# cpu.net
KiCad netlist of a schematic drawn in EAGLE
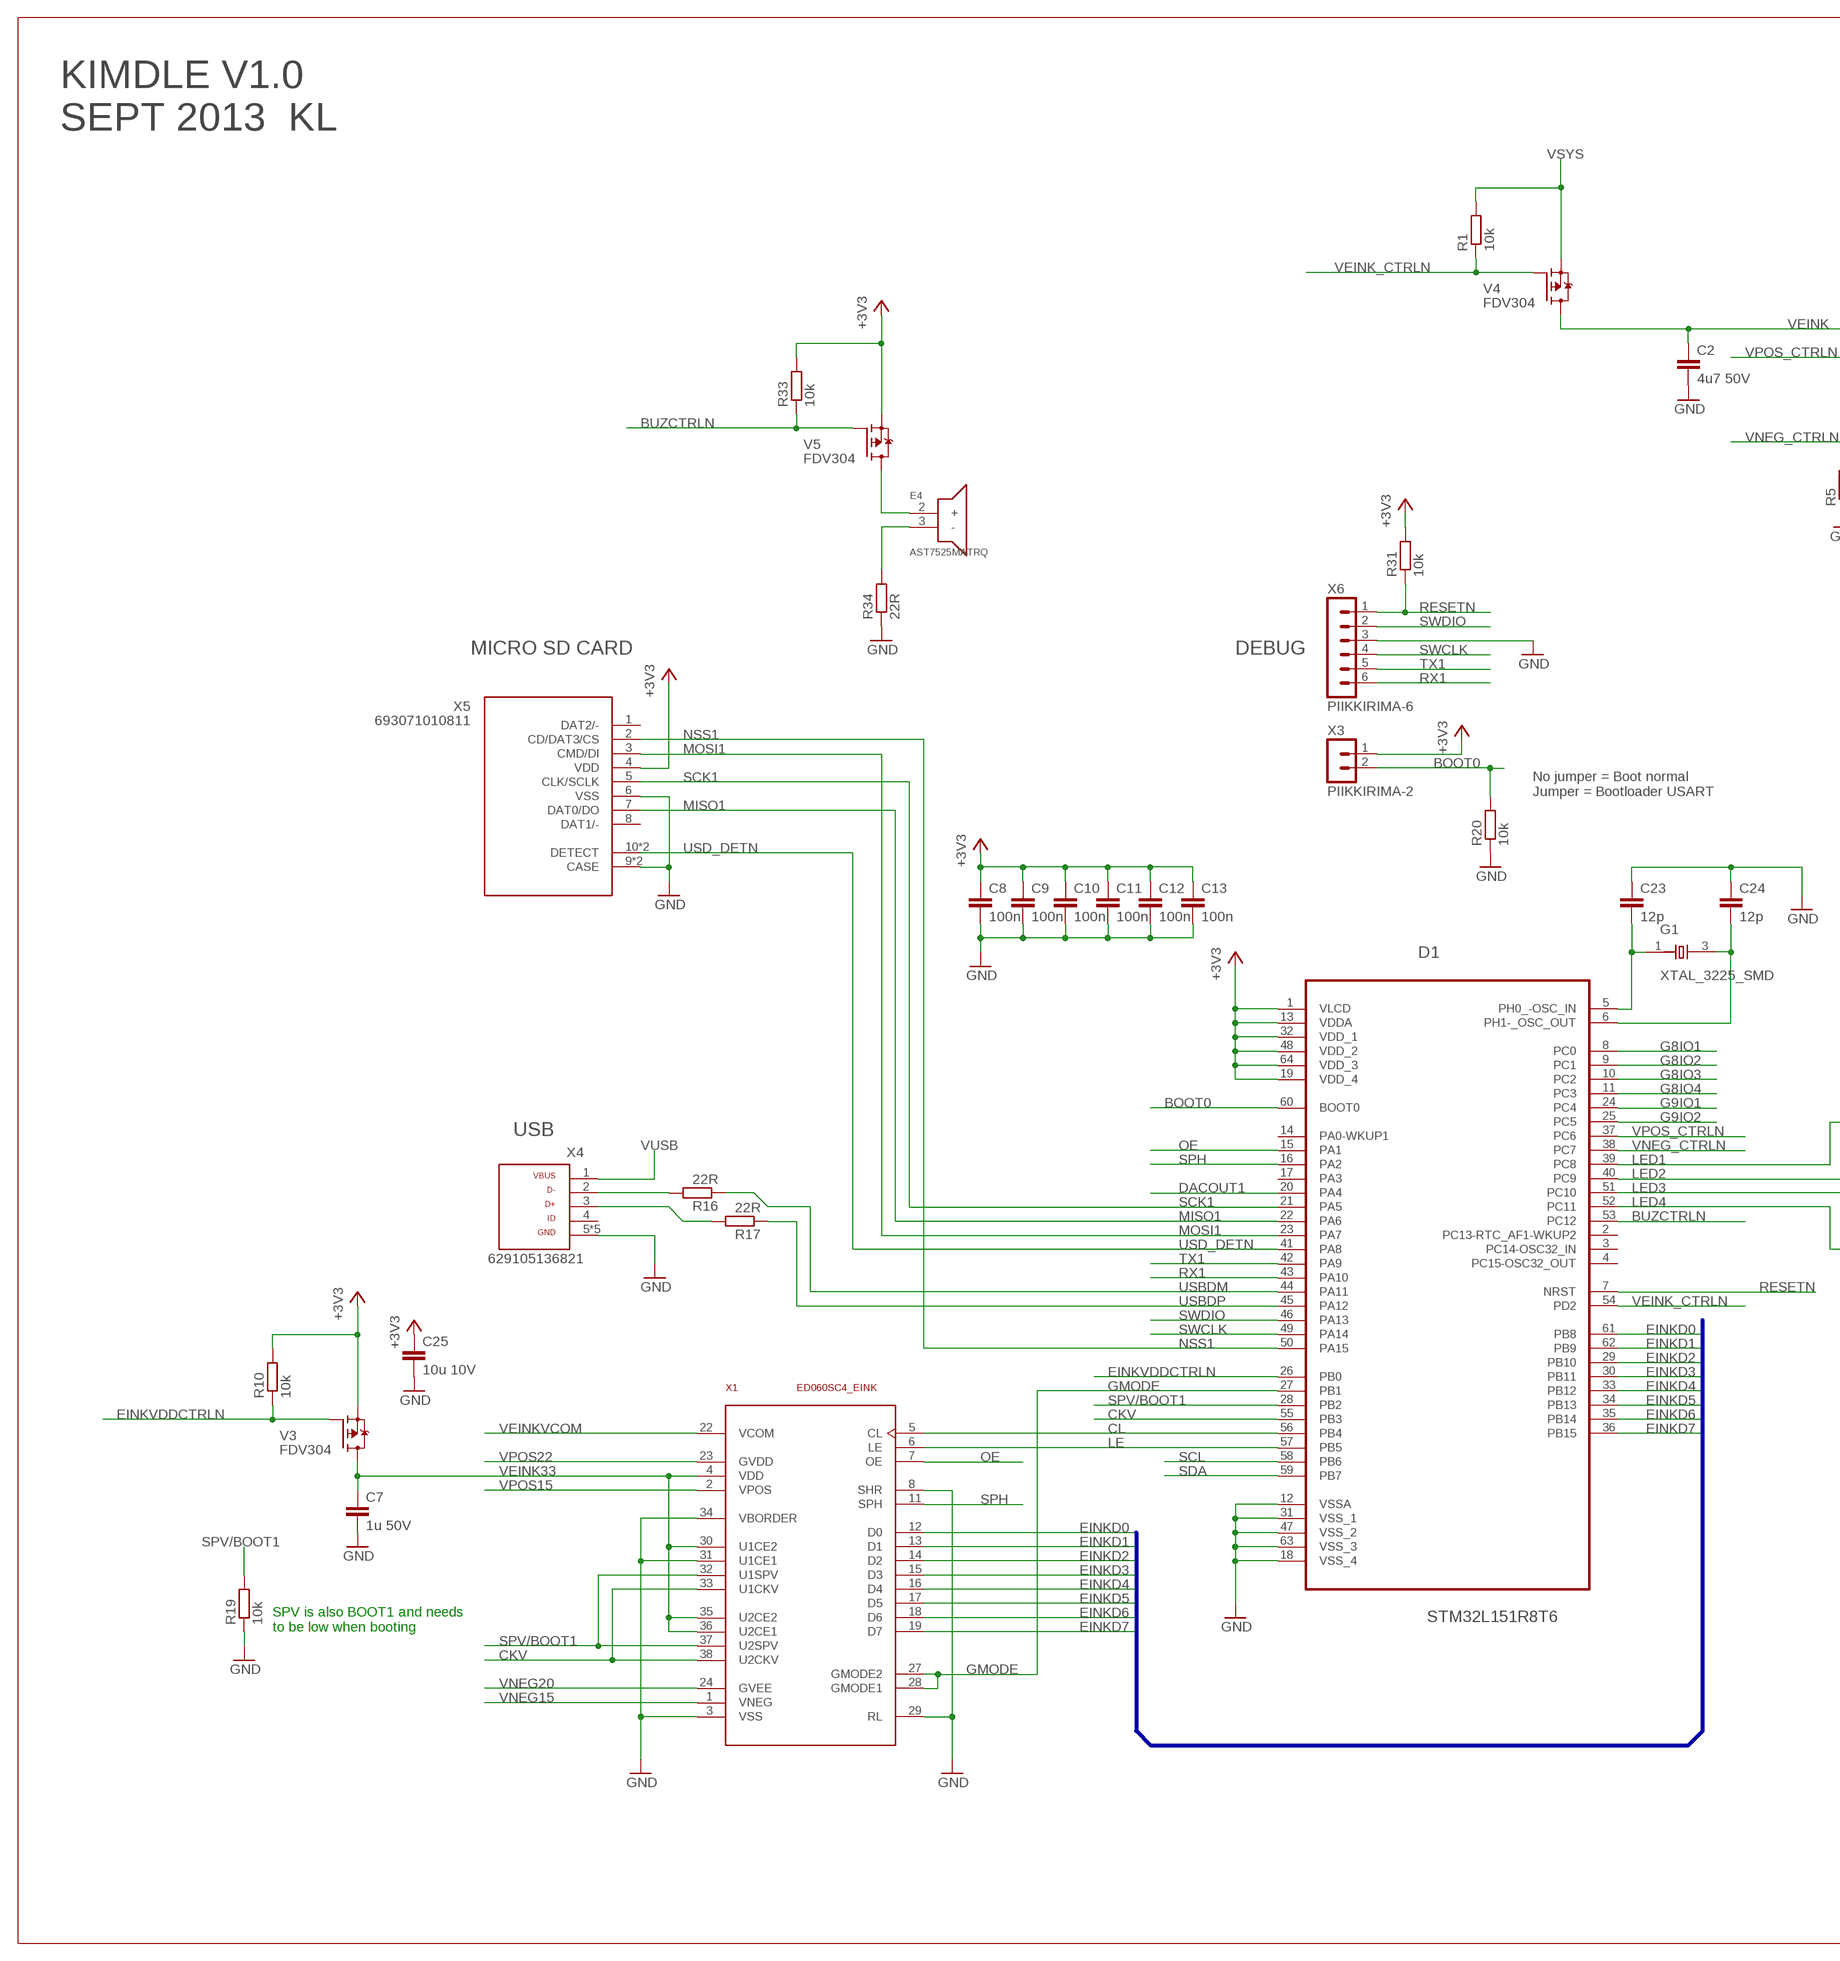
[diagram p0: schematic, sheet 1, part 1 of 2]
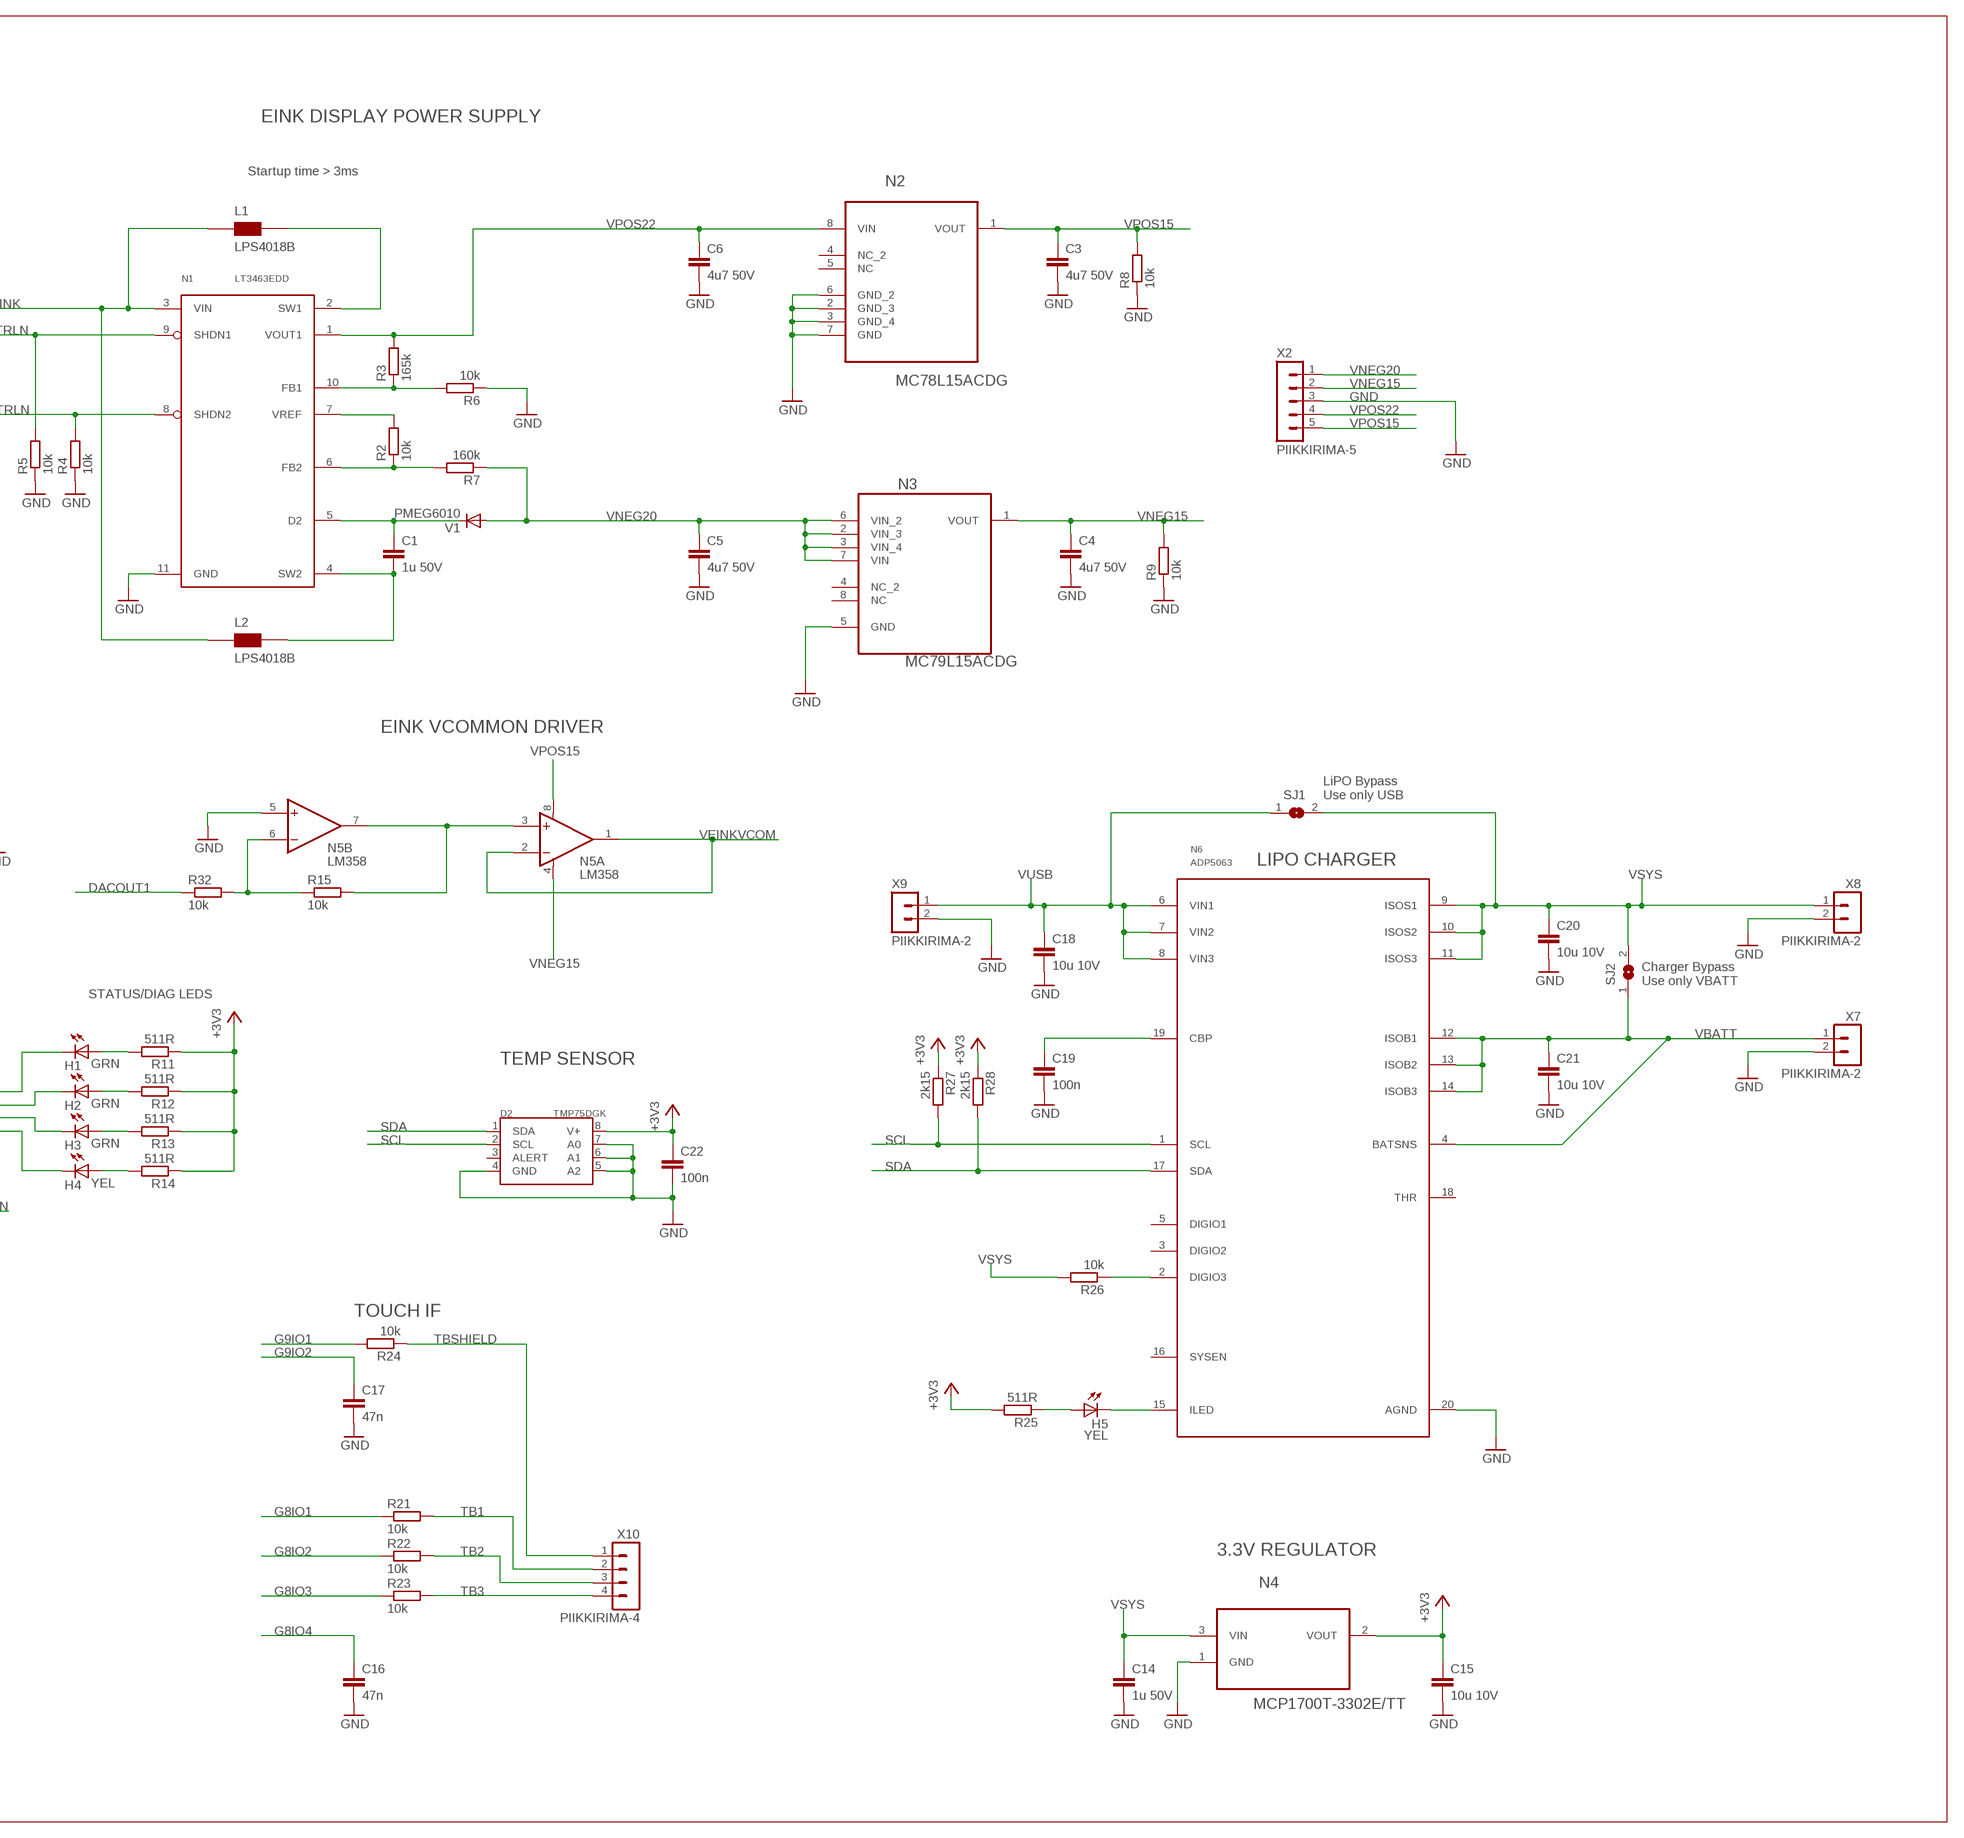
[diagram p1: schematic, sheet 1, part 2 of 2]

(export (version "E")
  (design (tool "Eeschema 10.0.6"))
  (components
    (comp (ref "C1")
      (value "1u 50V")
      (footprint "eagle-import:C0805")
      (libsource (lib "eagle-import") (part "C-EUC0805"))
    )
    (comp (ref "C2")
      (value "4u7 50V")
      (footprint "eagle-import:C0805")
      (libsource (lib "eagle-import") (part "C-EUC0805"))
    )
    (comp (ref "C3")
      (value "4u7 50V")
      (footprint "eagle-import:C0805")
      (libsource (lib "eagle-import") (part "C-EUC0805"))
    )
    (comp (ref "C4")
      (value "4u7 50V")
      (footprint "eagle-import:C0805")
      (libsource (lib "eagle-import") (part "C-EUC0805"))
    )
    (comp (ref "C5")
      (value "4u7 50V")
      (footprint "eagle-import:C0805")
      (libsource (lib "eagle-import") (part "C-EUC0805"))
    )
    (comp (ref "C6")
      (value "4u7 50V")
      (footprint "eagle-import:C0805")
      (libsource (lib "eagle-import") (part "C-EUC0805"))
    )
    (comp (ref "C7")
      (value "1u 50V")
      (footprint "eagle-import:C0805")
      (libsource (lib "eagle-import") (part "C-EUC0805"))
    )
    (comp (ref "C8")
      (value "100n")
      (footprint "eagle-import:C0603")
      (libsource (lib "eagle-import") (part "C-EUC0603"))
    )
    (comp (ref "C9")
      (value "100n")
      (footprint "eagle-import:C0603")
      (libsource (lib "eagle-import") (part "C-EUC0603"))
    )
    (comp (ref "C10")
      (value "100n")
      (footprint "eagle-import:C0603")
      (libsource (lib "eagle-import") (part "C-EUC0603"))
    )
    (comp (ref "C11")
      (value "100n")
      (footprint "eagle-import:C0603")
      (libsource (lib "eagle-import") (part "C-EUC0603"))
    )
    (comp (ref "C12")
      (value "100n")
      (footprint "eagle-import:C0603")
      (libsource (lib "eagle-import") (part "C-EUC0603"))
    )
    (comp (ref "C13")
      (value "100n")
      (footprint "eagle-import:C0603")
      (libsource (lib "eagle-import") (part "C-EUC0603"))
    )
    (comp (ref "C14")
      (value "1u 50V")
      (footprint "eagle-import:C0805")
      (libsource (lib "eagle-import") (part "C-EUC0805"))
    )
    (comp (ref "C15")
      (value "10u 10V")
      (footprint "eagle-import:C0805")
      (libsource (lib "eagle-import") (part "C-EUC0805"))
    )
    (comp (ref "C16")
      (value "47n")
      (footprint "eagle-import:C0805")
      (libsource (lib "eagle-import") (part "C-EUC0805"))
    )
    (comp (ref "C17")
      (value "47n")
      (footprint "eagle-import:C0805")
      (libsource (lib "eagle-import") (part "C-EUC0805"))
    )
    (comp (ref "C18")
      (value "10u 10V")
      (footprint "eagle-import:C0805")
      (libsource (lib "eagle-import") (part "C-EUC0805"))
    )
    (comp (ref "C19")
      (value "100n")
      (footprint "eagle-import:C0603")
      (libsource (lib "eagle-import") (part "C-EUC0603"))
    )
    (comp (ref "C20")
      (value "10u 10V")
      (footprint "eagle-import:C0805")
      (libsource (lib "eagle-import") (part "C-EUC0805"))
    )
    (comp (ref "C21")
      (value "10u 10V")
      (footprint "eagle-import:C0805")
      (libsource (lib "eagle-import") (part "C-EUC0805"))
    )
    (comp (ref "C22")
      (value "100n")
      (footprint "eagle-import:C0603")
      (libsource (lib "eagle-import") (part "C-EUC0603"))
    )
    (comp (ref "C23")
      (value "12p")
      (footprint "eagle-import:C0603")
      (libsource (lib "eagle-import") (part "C-EUC0603"))
    )
    (comp (ref "C24")
      (value "12p")
      (footprint "eagle-import:C0603")
      (libsource (lib "eagle-import") (part "C-EUC0603"))
    )
    (comp (ref "C25")
      (value "10u 10V")
      (footprint "eagle-import:C0805")
      (libsource (lib "eagle-import") (part "C-EUC0805"))
    )
    (comp (ref "D1")
      (value "STM32L151R8T6")
      (footprint "eagle-import:QFP50P1200X1200X160-64N")
      (libsource (lib "eagle-import") (part "STM32L151R8T6"))
    )
    (comp (ref "D2")
      (value "TMP75DGK")
      (footprint "eagle-import:MSOP8")
      (libsource (lib "eagle-import") (part "TMP75DGK"))
    )
    (comp (ref "E4")
      (value "AST7525MATRQ")
      (footprint "eagle-import:AST7525MATRQ")
      (libsource (lib "eagle-import") (part "AST7525MATRQ"))
    )
    (comp (ref "G1")
      (value "XTAL_3225_SMD")
      (footprint "eagle-import:X_3225")
      (libsource (lib "eagle-import") (part "XTAL_3225_SMD"))
    )
    (comp (ref "H1")
      (value "GRN")
      (footprint "eagle-import:CHIP-LED0603")
      (libsource (lib "eagle-import") (part "LEDCHIP-LED0603"))
    )
    (comp (ref "H2")
      (value "GRN")
      (footprint "eagle-import:CHIP-LED0603")
      (libsource (lib "eagle-import") (part "LEDCHIP-LED0603"))
    )
    (comp (ref "H3")
      (value "GRN")
      (footprint "eagle-import:CHIP-LED0603")
      (libsource (lib "eagle-import") (part "LEDCHIP-LED0603"))
    )
    (comp (ref "H4")
      (value "YEL")
      (footprint "eagle-import:CHIP-LED0603")
      (libsource (lib "eagle-import") (part "LEDCHIP-LED0603"))
    )
    (comp (ref "H5")
      (value "YEL")
      (footprint "eagle-import:CHIP-LED0603")
      (libsource (lib "eagle-import") (part "LEDCHIP-LED0603"))
    )
    (comp (ref "L1")
      (value "LPS4018B")
      (footprint "eagle-import:LPS4018_V2")
      (libsource (lib "eagle-import") (part "LPS4018B"))
    )
    (comp (ref "L2")
      (value "LPS4018B")
      (footprint "eagle-import:LPS4018_V2")
      (libsource (lib "eagle-import") (part "LPS4018B"))
    )
    (comp (ref "N1")
      (value "LT3463EDD")
      (footprint "eagle-import:DFN300X300X80-11N")
      (libsource (lib "eagle-import") (part "LT3463EDD"))
    )
    (comp (ref "N2")
      (value "MC78L15ACDG")
      (footprint "eagle-import:SOIC127P600X175-8N")
      (libsource (lib "eagle-import") (part "MC78L15ACDG"))
    )
    (comp (ref "N3")
      (value "MC79L15ACDG")
      (footprint "eagle-import:SOIC127P600X175-8N")
      (libsource (lib "eagle-import") (part "MC79L15ACDG"))
    )
    (comp (ref "N4")
      (value "MCP1700T-3302E/TT")
      (footprint "eagle-import:SOT95P237X112-3N")
      (libsource (lib "eagle-import") (part "MCP1700T-3302E/TT"))
    )
    (comp (ref "N5")
      (value "LM358")
      (footprint "eagle-import:SOP65P490X110-8N")
      (libsource (lib "eagle-import") (part "MAX412CPAMSOP"))
    )
    (comp (ref "N6")
      (value "ADP5063")
      (footprint "eagle-import:QFN50P400X400X80-21N")
      (libsource (lib "eagle-import") (part "ADP5063"))
    )
    (comp (ref "R1")
      (value "10k")
      (footprint "eagle-import:R0603")
      (libsource (lib "eagle-import") (part "R-EU_R0603"))
    )
    (comp (ref "R2")
      (value "10k")
      (footprint "eagle-import:R0603")
      (libsource (lib "eagle-import") (part "R-EU_R0603"))
    )
    (comp (ref "R3")
      (value "165k")
      (footprint "eagle-import:R0603")
      (libsource (lib "eagle-import") (part "R-EU_R0603"))
    )
    (comp (ref "R4")
      (value "10k")
      (footprint "eagle-import:R0603")
      (libsource (lib "eagle-import") (part "R-EU_R0603"))
    )
    (comp (ref "R5")
      (value "10k")
      (footprint "eagle-import:R0603")
      (libsource (lib "eagle-import") (part "R-EU_R0603"))
    )
    (comp (ref "R6")
      (value "10k")
      (footprint "eagle-import:R0603")
      (libsource (lib "eagle-import") (part "R-EU_R0603"))
    )
    (comp (ref "R7")
      (value "160k")
      (footprint "eagle-import:R0603")
      (libsource (lib "eagle-import") (part "R-EU_R0603"))
    )
    (comp (ref "R8")
      (value "10k")
      (footprint "eagle-import:R0603")
      (libsource (lib "eagle-import") (part "R-EU_R0603"))
    )
    (comp (ref "R9")
      (value "10k")
      (footprint "eagle-import:R0603")
      (libsource (lib "eagle-import") (part "R-EU_R0603"))
    )
    (comp (ref "R10")
      (value "10k")
      (footprint "eagle-import:R0603")
      (libsource (lib "eagle-import") (part "R-EU_R0603"))
    )
    (comp (ref "R11")
      (value "511R")
      (footprint "eagle-import:R0603")
      (libsource (lib "eagle-import") (part "R-EU_R0603"))
    )
    (comp (ref "R12")
      (value "511R")
      (footprint "eagle-import:R0603")
      (libsource (lib "eagle-import") (part "R-EU_R0603"))
    )
    (comp (ref "R13")
      (value "511R")
      (footprint "eagle-import:R0603")
      (libsource (lib "eagle-import") (part "R-EU_R0603"))
    )
    (comp (ref "R14")
      (value "511R")
      (footprint "eagle-import:R0603")
      (libsource (lib "eagle-import") (part "R-EU_R0603"))
    )
    (comp (ref "R15")
      (value "10k")
      (footprint "eagle-import:R0603")
      (libsource (lib "eagle-import") (part "R-EU_R0603"))
    )
    (comp (ref "R16")
      (value "22R")
      (footprint "eagle-import:R0603")
      (libsource (lib "eagle-import") (part "R-EU_R0603"))
    )
    (comp (ref "R17")
      (value "22R")
      (footprint "eagle-import:R0603")
      (libsource (lib "eagle-import") (part "R-EU_R0603"))
    )
    (comp (ref "R19")
      (value "10k")
      (footprint "eagle-import:R0603")
      (libsource (lib "eagle-import") (part "R-EU_R0603"))
    )
    (comp (ref "R20")
      (value "10k")
      (footprint "eagle-import:R0603")
      (libsource (lib "eagle-import") (part "R-EU_R0603"))
    )
    (comp (ref "R21")
      (value "10k")
      (footprint "eagle-import:R0603")
      (libsource (lib "eagle-import") (part "R-EU_R0603"))
    )
    (comp (ref "R22")
      (value "10k")
      (footprint "eagle-import:R0603")
      (libsource (lib "eagle-import") (part "R-EU_R0603"))
    )
    (comp (ref "R23")
      (value "10k")
      (footprint "eagle-import:R0603")
      (libsource (lib "eagle-import") (part "R-EU_R0603"))
    )
    (comp (ref "R24")
      (value "10k")
      (footprint "eagle-import:R0603")
      (libsource (lib "eagle-import") (part "R-EU_R0603"))
    )
    (comp (ref "R25")
      (value "511R")
      (footprint "eagle-import:R0603")
      (libsource (lib "eagle-import") (part "R-EU_R0603"))
    )
    (comp (ref "R26")
      (value "10k")
      (footprint "eagle-import:R0603")
      (libsource (lib "eagle-import") (part "R-EU_R0603"))
    )
    (comp (ref "R27")
      (value "2k15")
      (footprint "eagle-import:R0603")
      (libsource (lib "eagle-import") (part "R-EU_R0603"))
    )
    (comp (ref "R28")
      (value "2k15")
      (footprint "eagle-import:R0603")
      (libsource (lib "eagle-import") (part "R-EU_R0603"))
    )
    (comp (ref "R31")
      (value "10k")
      (footprint "eagle-import:R0603")
      (libsource (lib "eagle-import") (part "R-EU_R0603"))
    )
    (comp (ref "R32")
      (value "10k")
      (footprint "eagle-import:R0603")
      (libsource (lib "eagle-import") (part "R-EU_R0603"))
    )
    (comp (ref "R33")
      (value "10k")
      (footprint "eagle-import:R0603")
      (libsource (lib "eagle-import") (part "R-EU_R0603"))
    )
    (comp (ref "R34")
      (value "22R")
      (footprint "eagle-import:R0603")
      (libsource (lib "eagle-import") (part "R-EU_R0603"))
    )
    (comp (ref "SJ1")
      (value "SJ")
      (footprint "eagle-import:SJ-SMALL")
      (libsource (lib "eagle-import") (part "SJ"))
    )
    (comp (ref "SJ2")
      (value "SJ")
      (footprint "eagle-import:SJ-SMALL")
      (libsource (lib "eagle-import") (part "SJ"))
    )
    (comp (ref "V1")
      (value "PMEG6010")
      (footprint "eagle-import:SOD323-R")
      (libsource (lib "eagle-import") (part "DIODE-SOD323-R"))
    )
    (comp (ref "V3")
      (value "FDV304")
      (footprint "eagle-import:SOT23")
      (libsource (lib "eagle-import") (part "DMG2307LSOT23"))
    )
    (comp (ref "V4")
      (value "FDV304")
      (footprint "eagle-import:SOT23")
      (libsource (lib "eagle-import") (part "DMG2307LSOT23"))
    )
    (comp (ref "V5")
      (value "FDV304")
      (footprint "eagle-import:SOT23")
      (libsource (lib "eagle-import") (part "DMG2307LSOT23"))
    )
    (comp (ref "X1")
      (value "ED060SC4_EINK")
      (footprint "eagle-import:FH26-39S-0.3SHW")
      (libsource (lib "eagle-import") (part "ED060SC4_EINK"))
    )
    (comp (ref "X2")
      (value "PIIKKIRIMA-5")
      (footprint "eagle-import:PIIKKIRIMA-5")
      (libsource (lib "eagle-import") (part "PIIKKIRIMA-5"))
    )
    (comp (ref "X3")
      (value "PIIKKIRIMA-2")
      (footprint "eagle-import:PIIKKIRIMA-2")
      (libsource (lib "eagle-import") (part "PIIKKIRIMA-2"))
    )
    (comp (ref "X4")
      (value "629105136821")
      (footprint "eagle-import:629105136821")
      (libsource (lib "eagle-import") (part "629105136821"))
    )
    (comp (ref "X5")
      (value "693071010811")
      (footprint "eagle-import:693071010811")
      (libsource (lib "eagle-import") (part "693071010811"))
    )
    (comp (ref "X6")
      (value "PIIKKIRIMA-6")
      (footprint "eagle-import:PIIKKIRIMA-6")
      (libsource (lib "eagle-import") (part "PIIKKIRIMA-6"))
    )
    (comp (ref "X7")
      (value "PIIKKIRIMA-2")
      (footprint "eagle-import:PIIKKIRIMA-2")
      (libsource (lib "eagle-import") (part "PIIKKIRIMA-2"))
    )
    (comp (ref "X8")
      (value "PIIKKIRIMA-2")
      (footprint "eagle-import:PIIKKIRIMA-2")
      (libsource (lib "eagle-import") (part "PIIKKIRIMA-2"))
    )
    (comp (ref "X9")
      (value "PIIKKIRIMA-2")
      (footprint "eagle-import:PIIKKIRIMA-2")
      (libsource (lib "eagle-import") (part "PIIKKIRIMA-2"))
    )
    (comp (ref "X10")
      (value "PIIKKIRIMA-4")
      (footprint "eagle-import:PIIKKIRIMA-4")
      (libsource (lib "eagle-import") (part "PIIKKIRIMA-4"))
    )
  )
  (nets
    (net (code "1") (name "+3V3") (class "Default")
      (node (ref "C10") (pin "1") (pinfunction "1_1") (pintype "passive"))
      (node (ref "C11") (pin "1") (pinfunction "1_1") (pintype "passive"))
      (node (ref "C12") (pin "1") (pinfunction "1_1") (pintype "passive"))
      (node (ref "C13") (pin "1") (pinfunction "1_1") (pintype "passive"))
      (node (ref "C15") (pin "1") (pinfunction "1_1") (pintype "passive"))
      (node (ref "C22") (pin "1") (pinfunction "1_1") (pintype "passive"))
      (node (ref "C25") (pin "1") (pinfunction "1_1") (pintype "passive"))
      (node (ref "C8") (pin "1") (pinfunction "1_1") (pintype "passive"))
      (node (ref "C9") (pin "1") (pinfunction "1_1") (pintype "passive"))
      (node (ref "D1") (pin "1") (pinfunction "VLCD_1") (pintype "power_in"))
      (node (ref "D1") (pin "13") (pinfunction "VDDA_13") (pintype "power_in"))
      (node (ref "D1") (pin "19") (pinfunction "VDD_4_19") (pintype "power_in"))
      (node (ref "D1") (pin "32") (pinfunction "VDD_1_32") (pintype "power_in"))
      (node (ref "D1") (pin "48") (pinfunction "VDD_2_48") (pintype "power_in"))
      (node (ref "D1") (pin "64") (pinfunction "VDD_3_64") (pintype "power_in"))
      (node (ref "D2") (pin "8") (pinfunction "V+_8") (pintype "bidirectional"))
      (node (ref "N4") (pin "2") (pinfunction "VOUT_2") (pintype "output"))
      (node (ref "R10") (pin "2") (pinfunction "2_2") (pintype "passive"))
      (node (ref "R11") (pin "1") (pinfunction "1_1") (pintype "passive"))
      (node (ref "R12") (pin "1") (pinfunction "1_1") (pintype "passive"))
      (node (ref "R13") (pin "1") (pinfunction "1_1") (pintype "passive"))
      (node (ref "R14") (pin "1") (pinfunction "1_1") (pintype "passive"))
      (node (ref "R25") (pin "2") (pinfunction "2_2") (pintype "passive"))
      (node (ref "R27") (pin "1") (pinfunction "1_1") (pintype "passive"))
      (node (ref "R28") (pin "1") (pinfunction "1_1") (pintype "passive"))
      (node (ref "R31") (pin "2") (pinfunction "2_2") (pintype "passive"))
      (node (ref "R33") (pin "2") (pinfunction "2_2") (pintype "passive"))
      (node (ref "V3") (pin "2") (pinfunction "S_2") (pintype "passive"))
      (node (ref "V5") (pin "2") (pinfunction "S_2") (pintype "passive"))
      (node (ref "X3") (pin "1") (pinfunction "1_1") (pintype "passive"))
      (node (ref "X5") (pin "4") (pinfunction "VDD_4") (pintype "bidirectional"))
    )
    (net (code "2") (name "/BOOT0") (class "Default")
      (node (ref "D1") (pin "60") (pinfunction "BOOT0_60") (pintype "input"))
      (node (ref "R20") (pin "2") (pinfunction "2_2") (pintype "passive"))
      (node (ref "X3") (pin "2") (pinfunction "2_2") (pintype "passive"))
    )
    (net (code "3") (name "/BUZCTRLN") (class "Default")
      (node (ref "D1") (pin "53") (pinfunction "PC12_53") (pintype "bidirectional"))
      (node (ref "R33") (pin "1") (pinfunction "1_1") (pintype "passive"))
      (node (ref "V5") (pin "1") (pinfunction "G_1") (pintype "passive"))
    )
    (net (code "4") (name "/CKV") (class "Default")
      (node (ref "D1") (pin "55") (pinfunction "PB3_55") (pintype "bidirectional"))
      (node (ref "X1") (pin "33") (pinfunction "U1CKV_33") (pintype "bidirectional"))
      (node (ref "X1") (pin "38") (pinfunction "U2CKV_38") (pintype "bidirectional"))
    )
    (net (code "5") (name "/CL") (class "Default")
      (node (ref "D1") (pin "56") (pinfunction "PB4_56") (pintype "bidirectional"))
      (node (ref "X1") (pin "5") (pinfunction "CL_5") (pintype "bidirectional"))
    )
    (net (code "6") (name "/DACOUT1") (class "Default")
      (node (ref "D1") (pin "20") (pinfunction "PA4_20") (pintype "bidirectional"))
      (node (ref "R32") (pin "1") (pinfunction "1_1") (pintype "passive"))
    )
    (net (code "7") (name "/EINKD0") (class "Default")
      (node (ref "D1") (pin "61") (pinfunction "PB8_61") (pintype "bidirectional"))
      (node (ref "X1") (pin "12") (pinfunction "D0_12") (pintype "bidirectional"))
    )
    (net (code "8") (name "/EINKD1") (class "Default")
      (node (ref "D1") (pin "62") (pinfunction "PB9_62") (pintype "bidirectional"))
      (node (ref "X1") (pin "13") (pinfunction "D1_13") (pintype "bidirectional"))
    )
    (net (code "9") (name "/EINKD2") (class "Default")
      (node (ref "D1") (pin "29") (pinfunction "PB10_29") (pintype "bidirectional"))
      (node (ref "X1") (pin "14") (pinfunction "D2_14") (pintype "bidirectional"))
    )
    (net (code "10") (name "/EINKD3") (class "Default")
      (node (ref "D1") (pin "30") (pinfunction "PB11_30") (pintype "bidirectional"))
      (node (ref "X1") (pin "15") (pinfunction "D3_15") (pintype "bidirectional"))
    )
    (net (code "11") (name "/EINKD4") (class "Default")
      (node (ref "D1") (pin "33") (pinfunction "PB12_33") (pintype "bidirectional"))
      (node (ref "X1") (pin "16") (pinfunction "D4_16") (pintype "bidirectional"))
    )
    (net (code "12") (name "/EINKD5") (class "Default")
      (node (ref "D1") (pin "34") (pinfunction "PB13_34") (pintype "bidirectional"))
      (node (ref "X1") (pin "17") (pinfunction "D5_17") (pintype "bidirectional"))
    )
    (net (code "13") (name "/EINKD6") (class "Default")
      (node (ref "D1") (pin "35") (pinfunction "PB14_35") (pintype "bidirectional"))
      (node (ref "X1") (pin "18") (pinfunction "D6_18") (pintype "bidirectional"))
    )
    (net (code "14") (name "/EINKD7") (class "Default")
      (node (ref "D1") (pin "36") (pinfunction "PB15_36") (pintype "bidirectional"))
      (node (ref "X1") (pin "19") (pinfunction "D7_19") (pintype "bidirectional"))
    )
    (net (code "15") (name "/EINKVDDCTRLN") (class "Default")
      (node (ref "D1") (pin "26") (pinfunction "PB0_26") (pintype "bidirectional"))
      (node (ref "R10") (pin "1") (pinfunction "1_1") (pintype "passive"))
      (node (ref "V3") (pin "1") (pinfunction "G_1") (pintype "passive"))
    )
    (net (code "16") (name "/G8IO1") (class "Default")
      (node (ref "D1") (pin "8") (pinfunction "PC0_8") (pintype "bidirectional"))
      (node (ref "R21") (pin "1") (pinfunction "1_1") (pintype "passive"))
    )
    (net (code "17") (name "/G8IO2") (class "Default")
      (node (ref "D1") (pin "9") (pinfunction "PC1_9") (pintype "bidirectional"))
      (node (ref "R22") (pin "1") (pinfunction "1_1") (pintype "passive"))
    )
    (net (code "18") (name "/G8IO3") (class "Default")
      (node (ref "D1") (pin "10") (pinfunction "PC2_10") (pintype "bidirectional"))
      (node (ref "R23") (pin "1") (pinfunction "1_1") (pintype "passive"))
    )
    (net (code "19") (name "/G8IO4") (class "Default")
      (node (ref "C16") (pin "1") (pinfunction "1_1") (pintype "passive"))
      (node (ref "D1") (pin "11") (pinfunction "PC3_11") (pintype "bidirectional"))
    )
    (net (code "20") (name "/G9IO1") (class "Default")
      (node (ref "D1") (pin "24") (pinfunction "PC4_24") (pintype "bidirectional"))
      (node (ref "R24") (pin "2") (pinfunction "2_2") (pintype "passive"))
    )
    (net (code "21") (name "/G9IO2") (class "Default")
      (node (ref "C17") (pin "1") (pinfunction "1_1") (pintype "passive"))
      (node (ref "D1") (pin "25") (pinfunction "PC5_25") (pintype "bidirectional"))
    )
    (net (code "22") (name "/GMODE") (class "Default")
      (node (ref "D1") (pin "27") (pinfunction "PB1_27") (pintype "bidirectional"))
      (node (ref "X1") (pin "27") (pinfunction "GMODE2_27") (pintype "bidirectional"))
      (node (ref "X1") (pin "28") (pinfunction "GMODE1_28") (pintype "bidirectional"))
    )
    (net (code "23") (name "/LE") (class "Default")
      (node (ref "D1") (pin "57") (pinfunction "PB5_57") (pintype "bidirectional"))
      (node (ref "X1") (pin "6") (pinfunction "LE_6") (pintype "bidirectional"))
    )
    (net (code "24") (name "/LED1") (class "Default")
      (node (ref "D1") (pin "39") (pinfunction "PC8_39") (pintype "bidirectional"))
      (node (ref "H1") (pin "C") (pinfunction "C_C") (pintype "passive"))
    )
    (net (code "25") (name "/LED2") (class "Default")
      (node (ref "D1") (pin "40") (pinfunction "PC9_40") (pintype "bidirectional"))
      (node (ref "H2") (pin "C") (pinfunction "C_C") (pintype "passive"))
    )
    (net (code "26") (name "/LED3") (class "Default")
      (node (ref "D1") (pin "51") (pinfunction "PC10_51") (pintype "bidirectional"))
      (node (ref "H3") (pin "C") (pinfunction "C_C") (pintype "passive"))
    )
    (net (code "27") (name "/LED4") (class "Default")
      (node (ref "D1") (pin "52") (pinfunction "PC11_52") (pintype "bidirectional"))
      (node (ref "H4") (pin "C") (pinfunction "C_C") (pintype "passive"))
    )
    (net (code "28") (name "/MISO1") (class "Default")
      (node (ref "D1") (pin "22") (pinfunction "PA6_22") (pintype "bidirectional"))
      (node (ref "X5") (pin "7") (pinfunction "DAT0/DO_7") (pintype "bidirectional"))
    )
    (net (code "29") (name "/MOSI1") (class "Default")
      (node (ref "D1") (pin "23") (pinfunction "PA7_23") (pintype "bidirectional"))
      (node (ref "X5") (pin "3") (pinfunction "CMD/DI_3") (pintype "bidirectional"))
    )
    (net (code "30") (name "/NSS1") (class "Default")
      (node (ref "D1") (pin "50") (pinfunction "PA15_50") (pintype "bidirectional"))
      (node (ref "X5") (pin "2") (pinfunction "CD/DAT3/CS_2") (pintype "bidirectional"))
    )
    (net (code "31") (name "/OE") (class "Default")
      (node (ref "D1") (pin "15") (pinfunction "PA1_15") (pintype "bidirectional"))
      (node (ref "X1") (pin "7") (pinfunction "OE_7") (pintype "bidirectional"))
    )
    (net (code "32") (name "/RESETN") (class "Default")
      (node (ref "D1") (pin "7") (pinfunction "NRST_7") (pintype "bidirectional"))
      (node (ref "R31") (pin "1") (pinfunction "1_1") (pintype "passive"))
      (node (ref "X6") (pin "1") (pinfunction "1_1") (pintype "passive"))
    )
    (net (code "33") (name "/RX1") (class "Default")
      (node (ref "D1") (pin "43") (pinfunction "PA10_43") (pintype "bidirectional"))
      (node (ref "X6") (pin "6") (pinfunction "6_6") (pintype "passive"))
    )
    (net (code "34") (name "/SCK1") (class "Default")
      (node (ref "D1") (pin "21") (pinfunction "PA5_21") (pintype "bidirectional"))
      (node (ref "X5") (pin "5") (pinfunction "CLK/SCLK_5") (pintype "bidirectional"))
    )
    (net (code "35") (name "/SCL") (class "Default")
      (node (ref "D1") (pin "58") (pinfunction "PB6_58") (pintype "bidirectional"))
      (node (ref "D2") (pin "2") (pinfunction "SCL_2") (pintype "bidirectional"))
      (node (ref "N6") (pin "1") (pinfunction "SCL_1") (pintype "bidirectional"))
      (node (ref "R27") (pin "2") (pinfunction "2_2") (pintype "passive"))
    )
    (net (code "36") (name "/SDA") (class "Default")
      (node (ref "D1") (pin "59") (pinfunction "PB7_59") (pintype "bidirectional"))
      (node (ref "D2") (pin "1") (pinfunction "SDA_1") (pintype "bidirectional"))
      (node (ref "N6") (pin "17") (pinfunction "SDA_17") (pintype "bidirectional"))
      (node (ref "R28") (pin "2") (pinfunction "2_2") (pintype "passive"))
    )
    (net (code "37") (name "/SPH") (class "Default")
      (node (ref "D1") (pin "16") (pinfunction "PA2_16") (pintype "bidirectional"))
      (node (ref "X1") (pin "11") (pinfunction "SPH_11") (pintype "bidirectional"))
    )
    (net (code "38") (name "/SPV{slash}BOOT1") (class "Default")
      (node (ref "D1") (pin "28") (pinfunction "PB2_28") (pintype "bidirectional"))
      (node (ref "R19") (pin "2") (pinfunction "2_2") (pintype "passive"))
      (node (ref "X1") (pin "32") (pinfunction "U1SPV_32") (pintype "bidirectional"))
      (node (ref "X1") (pin "37") (pinfunction "U2SPV_37") (pintype "bidirectional"))
    )
    (net (code "39") (name "/SWCLK") (class "Default")
      (node (ref "D1") (pin "49") (pinfunction "PA14_49") (pintype "bidirectional"))
      (node (ref "X6") (pin "4") (pinfunction "4_4") (pintype "passive"))
    )
    (net (code "40") (name "/SWDIO") (class "Default")
      (node (ref "D1") (pin "46") (pinfunction "PA13_46") (pintype "bidirectional"))
      (node (ref "X6") (pin "2") (pinfunction "2_2") (pintype "passive"))
    )
    (net (code "41") (name "/TB1") (class "Default")
      (node (ref "R21") (pin "2") (pinfunction "2_2") (pintype "passive"))
      (node (ref "X10") (pin "2") (pinfunction "2_2") (pintype "passive"))
    )
    (net (code "42") (name "/TB2") (class "Default")
      (node (ref "R22") (pin "2") (pinfunction "2_2") (pintype "passive"))
      (node (ref "X10") (pin "3") (pinfunction "3_3") (pintype "passive"))
    )
    (net (code "43") (name "/TB3") (class "Default")
      (node (ref "R23") (pin "2") (pinfunction "2_2") (pintype "passive"))
      (node (ref "X10") (pin "4") (pinfunction "4_4") (pintype "passive"))
    )
    (net (code "44") (name "/TBSHIELD") (class "Default")
      (node (ref "R24") (pin "1") (pinfunction "1_1") (pintype "passive"))
      (node (ref "X10") (pin "1") (pinfunction "1_1") (pintype "passive"))
    )
    (net (code "45") (name "/TX1") (class "Default")
      (node (ref "D1") (pin "42") (pinfunction "PA9_42") (pintype "bidirectional"))
      (node (ref "X6") (pin "5") (pinfunction "5_5") (pintype "passive"))
    )
    (net (code "46") (name "/USBDM") (class "Default")
      (node (ref "D1") (pin "44") (pinfunction "PA11_44") (pintype "bidirectional"))
      (node (ref "R16") (pin "1") (pinfunction "1_1") (pintype "passive"))
    )
    (net (code "47") (name "/USBDP") (class "Default")
      (node (ref "D1") (pin "45") (pinfunction "PA12_45") (pintype "bidirectional"))
      (node (ref "R17") (pin "1") (pinfunction "1_1") (pintype "passive"))
    )
    (net (code "48") (name "/USD_DETN") (class "Default")
      (node (ref "D1") (pin "41") (pinfunction "PA8_41") (pintype "bidirectional"))
      (node (ref "X5") (pin "10") (pinfunction "DETECT_10") (pintype "bidirectional"))
      (node (ref "X5") (pin "10B") (pinfunction "DETECT_10B") (pintype "bidirectional"))
    )
    (net (code "49") (name "/VBATT") (class "Default")
      (node (ref "C21") (pin "1") (pinfunction "1_1") (pintype "passive"))
      (node (ref "N6") (pin "12") (pinfunction "ISOB1_12") (pintype "bidirectional"))
      (node (ref "N6") (pin "13") (pinfunction "ISOB2_13") (pintype "bidirectional"))
      (node (ref "N6") (pin "14") (pinfunction "ISOB3_14") (pintype "bidirectional"))
      (node (ref "N6") (pin "4") (pinfunction "BATSNS_4") (pintype "bidirectional"))
      (node (ref "SJ2") (pin "1") (pinfunction "1_1") (pintype "passive"))
      (node (ref "X7") (pin "1") (pinfunction "1_1") (pintype "passive"))
    )
    (net (code "50") (name "/VEINK") (class "Default")
      (node (ref "C2") (pin "1") (pinfunction "1_1") (pintype "passive"))
      (node (ref "L1") (pin "1") (pinfunction "A_1") (pintype "bidirectional"))
      (node (ref "L2") (pin "1") (pinfunction "A_1") (pintype "bidirectional"))
      (node (ref "N1") (pin "3") (pinfunction "VIN_3") (pintype "bidirectional"))
      (node (ref "V4") (pin "3") (pinfunction "D_3") (pintype "passive"))
    )
    (net (code "51") (name "/VEINK33") (class "Default")
      (node (ref "C7") (pin "1") (pinfunction "1_1") (pintype "passive"))
      (node (ref "V3") (pin "3") (pinfunction "D_3") (pintype "passive"))
      (node (ref "X1") (pin "30") (pinfunction "U1CE2_30") (pintype "bidirectional"))
      (node (ref "X1") (pin "35") (pinfunction "U2CE2_35") (pintype "bidirectional"))
      (node (ref "X1") (pin "36") (pinfunction "U2CE1_36") (pintype "bidirectional"))
      (node (ref "X1") (pin "4") (pinfunction "VDD_4") (pintype "bidirectional"))
    )
    (net (code "52") (name "/VEINKVCOM") (class "Default")
      (node (ref "N5") (pin "1") (pinfunction "OUT_1") (pintype "output"))
      (node (ref "N5") (pin "2") (pinfunction "-IN_2") (pintype "input"))
      (node (ref "X1") (pin "22") (pinfunction "VCOM_22") (pintype "bidirectional"))
    )
    (net (code "53") (name "/VEINK_CTRLN") (class "Default")
      (node (ref "D1") (pin "54") (pinfunction "PD2_54") (pintype "bidirectional"))
      (node (ref "R1") (pin "1") (pinfunction "1_1") (pintype "passive"))
      (node (ref "V4") (pin "1") (pinfunction "G_1") (pintype "passive"))
    )
    (net (code "54") (name "/VNEG15") (class "Default")
      (node (ref "C4") (pin "1") (pinfunction "1_1") (pintype "passive"))
      (node (ref "N3") (pin "1") (pinfunction "VOUT_1") (pintype "output"))
      (node (ref "N5") (pin "4") (pinfunction "V-_4") (pintype "power_in"))
      (node (ref "R9") (pin "2") (pinfunction "2_2") (pintype "passive"))
      (node (ref "X1") (pin "1") (pinfunction "VNEG_1") (pintype "bidirectional"))
      (node (ref "X2") (pin "2") (pinfunction "2_2") (pintype "passive"))
    )
    (net (code "55") (name "/VNEG20") (class "Default")
      (node (ref "C5") (pin "1") (pinfunction "1_1") (pintype "passive"))
      (node (ref "N3") (pin "2") (pinfunction "VIN_3_2") (pintype "power_in"))
      (node (ref "N3") (pin "3") (pinfunction "VIN_4_3") (pintype "power_in"))
      (node (ref "N3") (pin "6") (pinfunction "VIN_2_6") (pintype "power_in"))
      (node (ref "N3") (pin "7") (pinfunction "VIN_7") (pintype "power_in"))
      (node (ref "R7") (pin "1") (pinfunction "1_1") (pintype "passive"))
      (node (ref "V1") (pin "A") (pinfunction "A_A") (pintype "passive"))
      (node (ref "X1") (pin "24") (pinfunction "GVEE_24") (pintype "bidirectional"))
      (node (ref "X2") (pin "1") (pinfunction "1_1") (pintype "passive"))
    )
    (net (code "56") (name "/VNEG_CTRLN") (class "Default")
      (node (ref "D1") (pin "38") (pinfunction "PC7_38") (pintype "bidirectional"))
      (node (ref "N1") (pin "8") (pinfunction "SHDN2_8") (pintype "bidirectional"))
      (node (ref "R4") (pin "2") (pinfunction "2_2") (pintype "passive"))
    )
    (net (code "57") (name "/VPOS15") (class "Default")
      (node (ref "C3") (pin "1") (pinfunction "1_1") (pintype "passive"))
      (node (ref "N2") (pin "1") (pinfunction "VOUT_1") (pintype "output"))
      (node (ref "N5") (pin "8") (pinfunction "V+_8") (pintype "power_in"))
      (node (ref "R8") (pin "2") (pinfunction "2_2") (pintype "passive"))
      (node (ref "X1") (pin "2") (pinfunction "VPOS_2") (pintype "bidirectional"))
      (node (ref "X2") (pin "5") (pinfunction "5_5") (pintype "passive"))
    )
    (net (code "58") (name "/VPOS22") (class "Default")
      (node (ref "C6") (pin "1") (pinfunction "1_1") (pintype "passive"))
      (node (ref "N1") (pin "1") (pinfunction "VOUT1_1") (pintype "bidirectional"))
      (node (ref "N2") (pin "8") (pinfunction "VIN_8") (pintype "power_in"))
      (node (ref "R3") (pin "2") (pinfunction "2_2") (pintype "passive"))
      (node (ref "X1") (pin "23") (pinfunction "GVDD_23") (pintype "bidirectional"))
      (node (ref "X2") (pin "4") (pinfunction "4_4") (pintype "passive"))
    )
    (net (code "59") (name "/VPOS_CTRLN") (class "Default")
      (node (ref "D1") (pin "37") (pinfunction "PC6_37") (pintype "bidirectional"))
      (node (ref "N1") (pin "9") (pinfunction "SHDN1_9") (pintype "bidirectional"))
      (node (ref "R5") (pin "2") (pinfunction "2_2") (pintype "passive"))
    )
    (net (code "60") (name "/VSYS") (class "Default")
      (node (ref "C14") (pin "1") (pinfunction "1_1") (pintype "passive"))
      (node (ref "C20") (pin "1") (pinfunction "1_1") (pintype "passive"))
      (node (ref "N4") (pin "3") (pinfunction "VIN_3") (pintype "input"))
      (node (ref "N6") (pin "10") (pinfunction "ISOS2_10") (pintype "bidirectional"))
      (node (ref "N6") (pin "11") (pinfunction "ISOS3_11") (pintype "bidirectional"))
      (node (ref "N6") (pin "9") (pinfunction "ISOS1_9") (pintype "bidirectional"))
      (node (ref "R1") (pin "2") (pinfunction "2_2") (pintype "passive"))
      (node (ref "R26") (pin "2") (pinfunction "2_2") (pintype "passive"))
      (node (ref "SJ1") (pin "2") (pinfunction "2_2") (pintype "passive"))
      (node (ref "SJ2") (pin "2") (pinfunction "2_2") (pintype "passive"))
      (node (ref "V4") (pin "2") (pinfunction "S_2") (pintype "passive"))
      (node (ref "X8") (pin "1") (pinfunction "1_1") (pintype "passive"))
    )
    (net (code "61") (name "/VUSB") (class "Default")
      (node (ref "C18") (pin "1") (pinfunction "1_1") (pintype "passive"))
      (node (ref "N6") (pin "6") (pinfunction "VIN1_6") (pintype "bidirectional"))
      (node (ref "N6") (pin "7") (pinfunction "VIN2_7") (pintype "bidirectional"))
      (node (ref "N6") (pin "8") (pinfunction "VIN3_8") (pintype "bidirectional"))
      (node (ref "SJ1") (pin "1") (pinfunction "1_1") (pintype "passive"))
      (node (ref "X4") (pin "1") (pinfunction "1_1") (pintype "passive"))
      (node (ref "X9") (pin "1") (pinfunction "1_1") (pintype "passive"))
    )
    (net (code "62") (name "GND") (class "Default")
      (node (ref "C10") (pin "2") (pinfunction "2_2") (pintype "passive"))
      (node (ref "C11") (pin "2") (pinfunction "2_2") (pintype "passive"))
      (node (ref "C12") (pin "2") (pinfunction "2_2") (pintype "passive"))
      (node (ref "C13") (pin "2") (pinfunction "2_2") (pintype "passive"))
      (node (ref "C14") (pin "2") (pinfunction "2_2") (pintype "passive"))
      (node (ref "C15") (pin "2") (pinfunction "2_2") (pintype "passive"))
      (node (ref "C16") (pin "2") (pinfunction "2_2") (pintype "passive"))
      (node (ref "C17") (pin "2") (pinfunction "2_2") (pintype "passive"))
      (node (ref "C18") (pin "2") (pinfunction "2_2") (pintype "passive"))
      (node (ref "C19") (pin "2") (pinfunction "2_2") (pintype "passive"))
      (node (ref "C2") (pin "2") (pinfunction "2_2") (pintype "passive"))
      (node (ref "C20") (pin "2") (pinfunction "2_2") (pintype "passive"))
      (node (ref "C21") (pin "2") (pinfunction "2_2") (pintype "passive"))
      (node (ref "C22") (pin "2") (pinfunction "2_2") (pintype "passive"))
      (node (ref "C23") (pin "1") (pinfunction "1_1") (pintype "passive"))
      (node (ref "C24") (pin "1") (pinfunction "1_1") (pintype "passive"))
      (node (ref "C25") (pin "2") (pinfunction "2_2") (pintype "passive"))
      (node (ref "C3") (pin "2") (pinfunction "2_2") (pintype "passive"))
      (node (ref "C4") (pin "2") (pinfunction "2_2") (pintype "passive"))
      (node (ref "C5") (pin "2") (pinfunction "2_2") (pintype "passive"))
      (node (ref "C6") (pin "2") (pinfunction "2_2") (pintype "passive"))
      (node (ref "C7") (pin "2") (pinfunction "2_2") (pintype "passive"))
      (node (ref "C8") (pin "2") (pinfunction "2_2") (pintype "passive"))
      (node (ref "C9") (pin "2") (pinfunction "2_2") (pintype "passive"))
      (node (ref "D1") (pin "12") (pinfunction "VSSA_12") (pintype "power_in"))
      (node (ref "D1") (pin "18") (pinfunction "VSS_4_18") (pintype "power_in"))
      (node (ref "D1") (pin "31") (pinfunction "VSS_1_31") (pintype "power_in"))
      (node (ref "D1") (pin "47") (pinfunction "VSS_2_47") (pintype "power_in"))
      (node (ref "D1") (pin "63") (pinfunction "VSS_3_63") (pintype "power_in"))
      (node (ref "D2") (pin "4") (pinfunction "GND_4") (pintype "bidirectional"))
      (node (ref "D2") (pin "5") (pinfunction "A2_5") (pintype "bidirectional"))
      (node (ref "D2") (pin "6") (pinfunction "A1_6") (pintype "bidirectional"))
      (node (ref "D2") (pin "7") (pinfunction "A0_7") (pintype "bidirectional"))
      (node (ref "N1") (pin "11") (pinfunction "GND_11") (pintype "bidirectional"))
      (node (ref "N2") (pin "2") (pinfunction "GND_3_2") (pintype "passive"))
      (node (ref "N2") (pin "3") (pinfunction "GND_4_3") (pintype "passive"))
      (node (ref "N2") (pin "6") (pinfunction "GND_2_6") (pintype "passive"))
      (node (ref "N2") (pin "7") (pinfunction "GND_7") (pintype "passive"))
      (node (ref "N3") (pin "5") (pinfunction "GND_5") (pintype "passive"))
      (node (ref "N4") (pin "1") (pinfunction "GND_1") (pintype "passive"))
      (node (ref "N5") (pin "5") (pinfunction "+IN_5") (pintype "input"))
      (node (ref "N6") (pin "20") (pinfunction "AGND_20") (pintype "bidirectional"))
      (node (ref "R19") (pin "1") (pinfunction "1_1") (pintype "passive"))
      (node (ref "R20") (pin "1") (pinfunction "1_1") (pintype "passive"))
      (node (ref "R34") (pin "1") (pinfunction "1_1") (pintype "passive"))
      (node (ref "R4") (pin "1") (pinfunction "1_1") (pintype "passive"))
      (node (ref "R5") (pin "1") (pinfunction "1_1") (pintype "passive"))
      (node (ref "R6") (pin "1") (pinfunction "1_1") (pintype "passive"))
      (node (ref "R8") (pin "1") (pinfunction "1_1") (pintype "passive"))
      (node (ref "R9") (pin "1") (pinfunction "1_1") (pintype "passive"))
      (node (ref "X1") (pin "29") (pinfunction "RL_29") (pintype "bidirectional"))
      (node (ref "X1") (pin "3") (pinfunction "VSS_3") (pintype "bidirectional"))
      (node (ref "X1") (pin "31") (pinfunction "U1CE1_31") (pintype "bidirectional"))
      (node (ref "X1") (pin "34") (pinfunction "VBORDER_34") (pintype "bidirectional"))
      (node (ref "X1") (pin "8") (pinfunction "SHR_8") (pintype "bidirectional"))
      (node (ref "X2") (pin "3") (pinfunction "3_3") (pintype "passive"))
      (node (ref "X4") (pin "5") (pinfunction "5_5") (pintype "passive"))
      (node (ref "X4") (pin "Z1") (pinfunction "5_Z1") (pintype "passive"))
      (node (ref "X4") (pin "Z2") (pinfunction "5_Z2") (pintype "passive"))
      (node (ref "X4") (pin "Z3") (pinfunction "5_Z3") (pintype "passive"))
      (node (ref "X4") (pin "Z4") (pinfunction "5_Z4") (pintype "passive"))
      (node (ref "X5") (pin "6") (pinfunction "VSS_6") (pintype "bidirectional"))
      (node (ref "X5") (pin "9") (pinfunction "CASE_9") (pintype "bidirectional"))
      (node (ref "X5") (pin "9B") (pinfunction "CASE_9B") (pintype "bidirectional"))
      (node (ref "X6") (pin "3") (pinfunction "3_3") (pintype "passive"))
      (node (ref "X7") (pin "2") (pinfunction "2_2") (pintype "passive"))
      (node (ref "X8") (pin "2") (pinfunction "2_2") (pintype "passive"))
      (node (ref "X9") (pin "2") (pinfunction "2_2") (pintype "passive"))
    )
    (net (code "63") (name "Net-(D1-PH0_-OSC_IN)") (class "Default")
      (node (ref "C23") (pin "2") (pinfunction "2_2") (pintype "passive"))
      (node (ref "D1") (pin "5") (pinfunction "PH0_-OSC_IN_5") (pintype "bidirectional"))
      (node (ref "G1") (pin "1") (pinfunction "X1_1") (pintype "bidirectional"))
    )
    (net (code "64") (name "Net-(D1-PH1-_OSC_OUT)") (class "Default")
      (node (ref "C24") (pin "2") (pinfunction "2_2") (pintype "passive"))
      (node (ref "D1") (pin "6") (pinfunction "PH1-_OSC_OUT_6") (pintype "bidirectional"))
      (node (ref "G1") (pin "3") (pinfunction "X2_3") (pintype "bidirectional"))
    )
    (net (code "65") (name "Net-(E4-+)") (class "Default")
      (node (ref "E4") (pin "2") (pinfunction "+_2") (pintype "bidirectional"))
      (node (ref "V5") (pin "3") (pinfunction "D_3") (pintype "passive"))
    )
    (net (code "66") (name "Net-(E4--)") (class "Default")
      (node (ref "E4") (pin "3") (pinfunction "-_3") (pintype "bidirectional"))
      (node (ref "R34") (pin "2") (pinfunction "2_2") (pintype "passive"))
    )
    (net (code "67") (name "Net-(H1-PadA)") (class "Default")
      (node (ref "H1") (pin "A") (pinfunction "A_A") (pintype "passive"))
      (node (ref "R11") (pin "2") (pinfunction "2_2") (pintype "passive"))
    )
    (net (code "68") (name "Net-(H2-PadA)") (class "Default")
      (node (ref "H2") (pin "A") (pinfunction "A_A") (pintype "passive"))
      (node (ref "R12") (pin "2") (pinfunction "2_2") (pintype "passive"))
    )
    (net (code "69") (name "Net-(H3-PadA)") (class "Default")
      (node (ref "H3") (pin "A") (pinfunction "A_A") (pintype "passive"))
      (node (ref "R13") (pin "2") (pinfunction "2_2") (pintype "passive"))
    )
    (net (code "70") (name "Net-(H4-PadA)") (class "Default")
      (node (ref "H4") (pin "A") (pinfunction "A_A") (pintype "passive"))
      (node (ref "R14") (pin "2") (pinfunction "2_2") (pintype "passive"))
    )
    (net (code "71") (name "Net-(H5-PadA)") (class "Default")
      (node (ref "H5") (pin "A") (pinfunction "A_A") (pintype "passive"))
      (node (ref "R25") (pin "1") (pinfunction "1_1") (pintype "passive"))
    )
    (net (code "72") (name "Net-(L1-B)") (class "Default")
      (node (ref "L1") (pin "2") (pinfunction "B_2") (pintype "bidirectional"))
      (node (ref "N1") (pin "2") (pinfunction "SW1_2") (pintype "bidirectional"))
    )
    (net (code "73") (name "Net-(L2-B)") (class "Default")
      (node (ref "C1") (pin "2") (pinfunction "2_2") (pintype "passive"))
      (node (ref "L2") (pin "2") (pinfunction "B_2") (pintype "bidirectional"))
      (node (ref "N1") (pin "4") (pinfunction "SW2_4") (pintype "bidirectional"))
    )
    (net (code "74") (name "Net-(N1-D2)") (class "Default")
      (node (ref "C1") (pin "1") (pinfunction "1_1") (pintype "passive"))
      (node (ref "N1") (pin "5") (pinfunction "D2_5") (pintype "bidirectional"))
      (node (ref "V1") (pin "C") (pinfunction "C_C") (pintype "passive"))
    )
    (net (code "75") (name "Net-(N1-FB1)") (class "Default")
      (node (ref "N1") (pin "10") (pinfunction "FB1_10") (pintype "bidirectional"))
      (node (ref "R3") (pin "1") (pinfunction "1_1") (pintype "passive"))
      (node (ref "R6") (pin "2") (pinfunction "2_2") (pintype "passive"))
    )
    (net (code "76") (name "Net-(N1-FB2)") (class "Default")
      (node (ref "N1") (pin "6") (pinfunction "FB2_6") (pintype "bidirectional"))
      (node (ref "R2") (pin "1") (pinfunction "1_1") (pintype "passive"))
      (node (ref "R7") (pin "2") (pinfunction "2_2") (pintype "passive"))
    )
    (net (code "77") (name "Net-(N1-VREF)") (class "Default")
      (node (ref "N1") (pin "7") (pinfunction "VREF_7") (pintype "bidirectional"))
      (node (ref "R2") (pin "2") (pinfunction "2_2") (pintype "passive"))
    )
    (net (code "78") (name "Net-(N5A-+IN)") (class "Default")
      (node (ref "N5") (pin "3") (pinfunction "+IN_3") (pintype "input"))
      (node (ref "N5") (pin "7") (pinfunction "OUT_7") (pintype "output"))
      (node (ref "R15") (pin "2") (pinfunction "2_2") (pintype "passive"))
    )
    (net (code "79") (name "Net-(N5B--IN)") (class "Default")
      (node (ref "N5") (pin "6") (pinfunction "-IN_6") (pintype "input"))
      (node (ref "R15") (pin "1") (pinfunction "1_1") (pintype "passive"))
      (node (ref "R32") (pin "2") (pinfunction "2_2") (pintype "passive"))
    )
    (net (code "80") (name "Net-(N6-CBP)") (class "Default")
      (node (ref "C19") (pin "1") (pinfunction "1_1") (pintype "passive"))
      (node (ref "N6") (pin "19") (pinfunction "CBP_19") (pintype "bidirectional"))
    )
    (net (code "81") (name "Net-(N6-DIGIO3)") (class "Default")
      (node (ref "N6") (pin "2") (pinfunction "DIGIO3_2") (pintype "bidirectional"))
      (node (ref "R26") (pin "1") (pinfunction "1_1") (pintype "passive"))
    )
    (net (code "82") (name "Net-(N6-ILED)") (class "Default")
      (node (ref "H5") (pin "C") (pinfunction "C_C") (pintype "passive"))
      (node (ref "N6") (pin "15") (pinfunction "ILED_15") (pintype "bidirectional"))
    )
    (net (code "83") (name "Net-(R16-Pad2)") (class "Default")
      (node (ref "R16") (pin "2") (pinfunction "2_2") (pintype "passive"))
      (node (ref "X4") (pin "2") (pinfunction "2_2") (pintype "passive"))
    )
    (net (code "84") (name "Net-(R17-Pad2)") (class "Default")
      (node (ref "R17") (pin "2") (pinfunction "2_2") (pintype "passive"))
      (node (ref "X4") (pin "3") (pinfunction "3_3") (pintype "passive"))
    )
    (net (code "85") (name "unconnected-(D1-PA0-WKUP1-Pad14)") (class "Default")
      (node (ref "D1") (pin "14") (pinfunction "PA0-WKUP1_14") (pintype "bidirectional"))
    )
    (net (code "86") (name "unconnected-(D1-PA3-Pad17)") (class "Default")
      (node (ref "D1") (pin "17") (pinfunction "PA3_17") (pintype "bidirectional"))
    )
    (net (code "87") (name "unconnected-(D1-PC13-RTC_AF1-WKUP2-Pad2)") (class "Default")
      (node (ref "D1") (pin "2") (pinfunction "PC13-RTC_AF1-WKUP2_2") (pintype "bidirectional"))
    )
    (net (code "88") (name "unconnected-(D1-PC14-OSC32_IN-Pad3)") (class "Default")
      (node (ref "D1") (pin "3") (pinfunction "PC14-OSC32_IN_3") (pintype "bidirectional"))
    )
    (net (code "89") (name "unconnected-(D1-PC15-OSC32_OUT-Pad4)") (class "Default")
      (node (ref "D1") (pin "4") (pinfunction "PC15-OSC32_OUT_4") (pintype "bidirectional"))
    )
    (net (code "90") (name "unconnected-(D2-ALERT-Pad3)") (class "Default")
      (node (ref "D2") (pin "3") (pinfunction "ALERT_3") (pintype "bidirectional"))
    )
    (net (code "91") (name "unconnected-(N2-NC-Pad5)") (class "Default")
      (node (ref "N2") (pin "5") (pinfunction "NC_5") (pintype "no_connect"))
    )
    (net (code "92") (name "unconnected-(N2-NC_2-Pad4)") (class "Default")
      (node (ref "N2") (pin "4") (pinfunction "NC_2_4") (pintype "no_connect"))
    )
    (net (code "93") (name "unconnected-(N3-NC-Pad8)") (class "Default")
      (node (ref "N3") (pin "8") (pinfunction "NC_8") (pintype "no_connect"))
    )
    (net (code "94") (name "unconnected-(N3-NC_2-Pad4)") (class "Default")
      (node (ref "N3") (pin "4") (pinfunction "NC_2_4") (pintype "no_connect"))
    )
    (net (code "95") (name "unconnected-(N6-DIGIO1-Pad5)") (class "Default")
      (node (ref "N6") (pin "5") (pinfunction "DIGIO1_5") (pintype "bidirectional"))
    )
    (net (code "96") (name "unconnected-(N6-DIGIO2-Pad3)") (class "Default")
      (node (ref "N6") (pin "3") (pinfunction "DIGIO2_3") (pintype "bidirectional"))
    )
    (net (code "97") (name "unconnected-(N6-SYSEN-Pad16)") (class "Default")
      (node (ref "N6") (pin "16") (pinfunction "SYSEN_16") (pintype "bidirectional"))
    )
    (net (code "98") (name "unconnected-(N6-THR-Pad18)") (class "Default")
      (node (ref "N6") (pin "18") (pinfunction "THR_18") (pintype "bidirectional"))
    )
    (net (code "99") (name "unconnected-(X4-Pad4)") (class "Default")
      (node (ref "X4") (pin "4") (pinfunction "4_4") (pintype "passive"))
    )
    (net (code "100") (name "unconnected-(X5-DAT1{slash}--Pad8)") (class "Default")
      (node (ref "X5") (pin "8") (pinfunction "DAT1/-_8") (pintype "bidirectional"))
    )
    (net (code "101") (name "unconnected-(X5-DAT2{slash}--Pad1)") (class "Default")
      (node (ref "X5") (pin "1") (pinfunction "DAT2/-_1") (pintype "bidirectional"))
    )
  )
)
